# PCB_Task_2020-06-05_09-06-46.net
KiCad netlist of a schematic drawn in EasyEDA
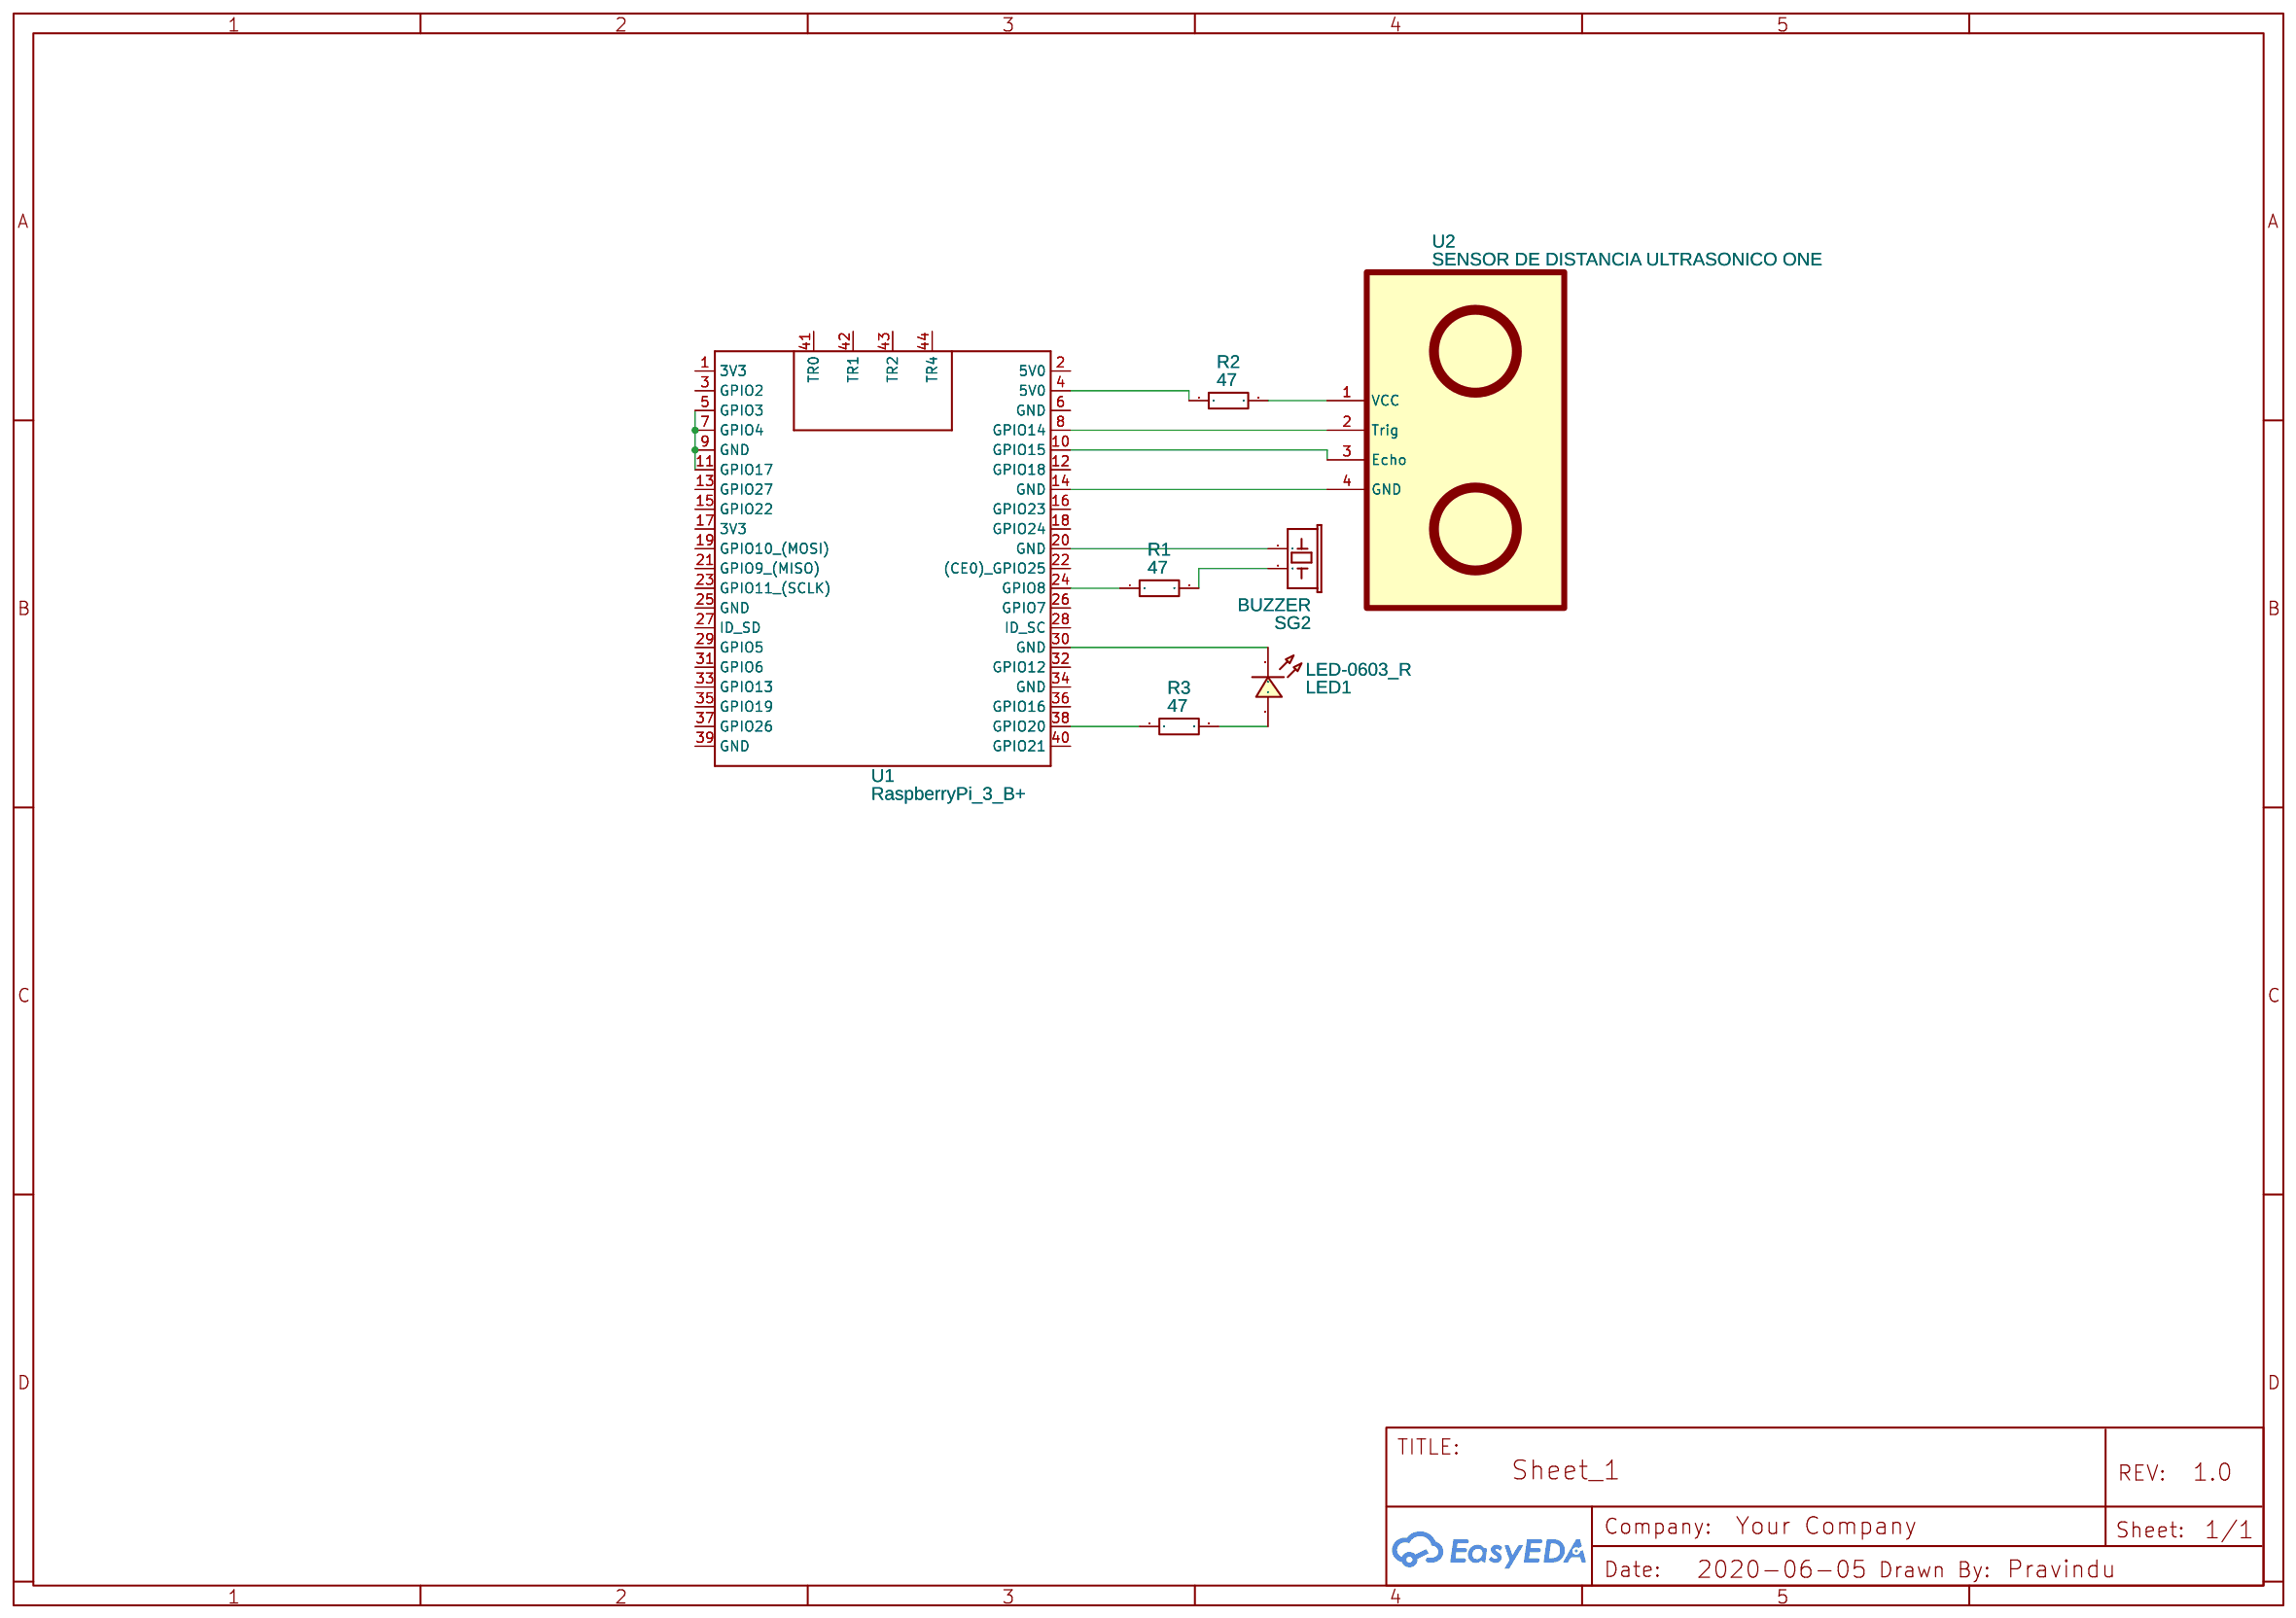
[diagram p0: schematic sheet]

(export (version "E")
  (design (tool "Eeschema 10.0.6"))
  (components
    (comp (ref "LED1")
      (value "LED-0603_R")
      (fields
        (field (name "BOM_Manufacturer Part") "19-217/R6C-AL1M2VY/3T")
        (field (name "BOM_Supplier Part") "C72044")
      )
      (libsource (lib "") (part "LED-0603_R"))
    )
    (comp (ref "R1")
      (value "47")
      (fields
        (field (name "BOM_Manufacturer Part") "KNP2W-47Ω±5% MK型")
        (field (name "BOM_Supplier Part") "C209824")
      )
      (libsource (lib "") (part "47Ω(470) ±5%"))
    )
    (comp (ref "R2")
      (value "47")
      (fields
        (field (name "BOM_Manufacturer Part") "KNP2W-47Ω±5% MK型")
        (field (name "BOM_Supplier Part") "C209824")
      )
      (libsource (lib "") (part "47Ω(470) ±5%"))
    )
    (comp (ref "R3")
      (value "47")
      (fields
        (field (name "BOM_Manufacturer Part") "KNP2W-47Ω±5% MK型")
        (field (name "BOM_Supplier Part") "C209824")
      )
      (libsource (lib "") (part "47Ω(470) ±5%"))
    )
    (comp (ref "SG2") (value "BUZZER") (libsource (lib "") (part "BUZZER")))
    (comp (ref "U1")
      (value "RaspberryPi_3_B+")
      (fields (field (name "BOM_Manufacturer Part") "RaspberryPi 3"))
      (libsource (lib "") (part "RaspberryPi_3_B+"))
    )
    (comp (ref "U2")
      (value "SENSOR DE DISTANCIA ULTRASONICO ONE")
      (libsource (lib "") (part "SENSOR DE DISTANCIA ULTRASONICO ONE"))
    )
  )
  (nets
    (net (code "1") (name "Net-(LED1-Pad1)") (class "Default")
      (node (ref "LED1") (pin "1") (pinfunction "1_1") (pintype "unspecified"))
      (node (ref "R3") (pin "2") (pinfunction "2_2") (pintype "unspecified"))
    )
    (net (code "2") (name "Net-(LED1-Pad2)") (class "Default")
      (node (ref "LED1") (pin "2") (pinfunction "2_2") (pintype "unspecified"))
      (node (ref "U1") (pin "30") (pinfunction "GND_30") (pintype "unspecified"))
    )
    (net (code "3") (name "Net-(R1-Pad2)") (class "Default")
      (node (ref "R1") (pin "2") (pinfunction "2_2") (pintype "unspecified"))
      (node (ref "SG2") (pin "2") (pinfunction "2_2") (pintype "unspecified"))
    )
    (net (code "4") (name "Net-(R2-Pad1)") (class "Default")
      (node (ref "R2") (pin "1") (pinfunction "1_1") (pintype "unspecified"))
      (node (ref "U1") (pin "4") (pinfunction "5V0_4") (pintype "unspecified"))
    )
    (net (code "5") (name "Net-(SG2-Pad1)") (class "Default")
      (node (ref "SG2") (pin "1") (pinfunction "1_1") (pintype "unspecified"))
      (node (ref "U1") (pin "20") (pinfunction "GND_20") (pintype "unspecified"))
    )
    (net (code "6") (name "Net-(U1-GPIO8)") (class "Default")
      (node (ref "R1") (pin "1") (pinfunction "1_1") (pintype "unspecified"))
      (node (ref "U1") (pin "24") (pinfunction "GPIO8_24") (pintype "unspecified"))
    )
    (net (code "7") (name "Net-(U1-GPIO14)") (class "Default")
      (node (ref "U1") (pin "8") (pinfunction "GPIO14_8") (pintype "unspecified"))
      (node (ref "U2") (pin "2") (pinfunction "Trig_2") (pintype "unspecified"))
    )
    (net (code "8") (name "Net-(U1-GPIO15)") (class "Default")
      (node (ref "U1") (pin "10") (pinfunction "GPIO15_10") (pintype "unspecified"))
      (node (ref "U2") (pin "3") (pinfunction "Echo_3") (pintype "unspecified"))
    )
    (net (code "9") (name "Net-(U1-GPIO17)") (class "Default")
      (node (ref "U1") (pin "11") (pinfunction "GPIO17_11") (pintype "unspecified"))
      (node (ref "U1") (pin "5") (pinfunction "GPIO3_5") (pintype "unspecified"))
      (node (ref "U1") (pin "7") (pinfunction "GPIO4_7") (pintype "unspecified"))
      (node (ref "U1") (pin "9") (pinfunction "GND_9") (pintype "unspecified"))
    )
    (net (code "10") (name "Net-(U1-GPIO20)") (class "Default")
      (node (ref "R3") (pin "1") (pinfunction "1_1") (pintype "unspecified"))
      (node (ref "U1") (pin "38") (pinfunction "GPIO20_38") (pintype "unspecified"))
    )
    (net (code "11") (name "Net-(U2-GND)") (class "Default")
      (node (ref "U1") (pin "14") (pinfunction "GND_14") (pintype "unspecified"))
      (node (ref "U2") (pin "4") (pinfunction "GND_4") (pintype "unspecified"))
    )
    (net (code "12") (name "Net-(U2-VCC)") (class "Default")
      (node (ref "R2") (pin "2") (pinfunction "2_2") (pintype "unspecified"))
      (node (ref "U2") (pin "1") (pinfunction "VCC_1") (pintype "unspecified"))
    )
    (net (code "13") (name "unconnected-(U1-(CE0)_GPIO25-Pad22)") (class "Default")
      (node (ref "U1") (pin "22") (pinfunction "(CE0)_GPIO25_22") (pintype "unspecified"))
    )
    (net (code "14") (name "unconnected-(U1-3V3-Pad1)") (class "Default")
      (node (ref "U1") (pin "1") (pinfunction "3V3_1") (pintype "unspecified"))
    )
    (net (code "15") (name "unconnected-(U1-3V3-Pad17)") (class "Default")
      (node (ref "U1") (pin "17") (pinfunction "3V3_17") (pintype "unspecified"))
    )
    (net (code "16") (name "unconnected-(U1-5V0-Pad2)") (class "Default")
      (node (ref "U1") (pin "2") (pinfunction "5V0_2") (pintype "unspecified"))
    )
    (net (code "17") (name "unconnected-(U1-GND-Pad6)") (class "Default")
      (node (ref "U1") (pin "6") (pinfunction "GND_6") (pintype "unspecified"))
    )
    (net (code "18") (name "unconnected-(U1-GND-Pad25)") (class "Default")
      (node (ref "U1") (pin "25") (pinfunction "GND_25") (pintype "unspecified"))
    )
    (net (code "19") (name "unconnected-(U1-GND-Pad34)") (class "Default")
      (node (ref "U1") (pin "34") (pinfunction "GND_34") (pintype "unspecified"))
    )
    (net (code "20") (name "unconnected-(U1-GND-Pad39)") (class "Default")
      (node (ref "U1") (pin "39") (pinfunction "GND_39") (pintype "unspecified"))
    )
    (net (code "21") (name "unconnected-(U1-GPIO2-Pad3)") (class "Default")
      (node (ref "U1") (pin "3") (pinfunction "GPIO2_3") (pintype "unspecified"))
    )
    (net (code "22") (name "unconnected-(U1-GPIO5-Pad29)") (class "Default")
      (node (ref "U1") (pin "29") (pinfunction "GPIO5_29") (pintype "unspecified"))
    )
    (net (code "23") (name "unconnected-(U1-GPIO6-Pad31)") (class "Default")
      (node (ref "U1") (pin "31") (pinfunction "GPIO6_31") (pintype "unspecified"))
    )
    (net (code "24") (name "unconnected-(U1-GPIO7-Pad26)") (class "Default")
      (node (ref "U1") (pin "26") (pinfunction "GPIO7_26") (pintype "unspecified"))
    )
    (net (code "25") (name "unconnected-(U1-GPIO9_(MISO)-Pad21)") (class "Default")
      (node (ref "U1") (pin "21") (pinfunction "GPIO9_(MISO)_21") (pintype "unspecified"))
    )
    (net (code "26") (name "unconnected-(U1-GPIO10_(MOSI)-Pad19)") (class "Default")
      (node (ref "U1") (pin "19") (pinfunction "GPIO10_(MOSI)_19") (pintype "unspecified"))
    )
    (net (code "27") (name "unconnected-(U1-GPIO11_(SCLK)-Pad23)") (class "Default")
      (node (ref "U1") (pin "23") (pinfunction "GPIO11_(SCLK)_23") (pintype "unspecified"))
    )
    (net (code "28") (name "unconnected-(U1-GPIO12-Pad32)") (class "Default")
      (node (ref "U1") (pin "32") (pinfunction "GPIO12_32") (pintype "unspecified"))
    )
    (net (code "29") (name "unconnected-(U1-GPIO13-Pad33)") (class "Default")
      (node (ref "U1") (pin "33") (pinfunction "GPIO13_33") (pintype "unspecified"))
    )
    (net (code "30") (name "unconnected-(U1-GPIO16-Pad36)") (class "Default")
      (node (ref "U1") (pin "36") (pinfunction "GPIO16_36") (pintype "unspecified"))
    )
    (net (code "31") (name "unconnected-(U1-GPIO18-Pad12)") (class "Default")
      (node (ref "U1") (pin "12") (pinfunction "GPIO18_12") (pintype "unspecified"))
    )
    (net (code "32") (name "unconnected-(U1-GPIO19-Pad35)") (class "Default")
      (node (ref "U1") (pin "35") (pinfunction "GPIO19_35") (pintype "unspecified"))
    )
    (net (code "33") (name "unconnected-(U1-GPIO21-Pad40)") (class "Default")
      (node (ref "U1") (pin "40") (pinfunction "GPIO21_40") (pintype "unspecified"))
    )
    (net (code "34") (name "unconnected-(U1-GPIO22-Pad15)") (class "Default")
      (node (ref "U1") (pin "15") (pinfunction "GPIO22_15") (pintype "unspecified"))
    )
    (net (code "35") (name "unconnected-(U1-GPIO23-Pad16)") (class "Default")
      (node (ref "U1") (pin "16") (pinfunction "GPIO23_16") (pintype "unspecified"))
    )
    (net (code "36") (name "unconnected-(U1-GPIO24-Pad18)") (class "Default")
      (node (ref "U1") (pin "18") (pinfunction "GPIO24_18") (pintype "unspecified"))
    )
    (net (code "37") (name "unconnected-(U1-GPIO26-Pad37)") (class "Default")
      (node (ref "U1") (pin "37") (pinfunction "GPIO26_37") (pintype "unspecified"))
    )
    (net (code "38") (name "unconnected-(U1-GPIO27-Pad13)") (class "Default")
      (node (ref "U1") (pin "13") (pinfunction "GPIO27_13") (pintype "unspecified"))
    )
    (net (code "39") (name "unconnected-(U1-ID_SC-Pad28)") (class "Default")
      (node (ref "U1") (pin "28") (pinfunction "ID_SC_28") (pintype "unspecified"))
    )
    (net (code "40") (name "unconnected-(U1-ID_SD-Pad27)") (class "Default")
      (node (ref "U1") (pin "27") (pinfunction "ID_SD_27") (pintype "unspecified"))
    )
    (net (code "41") (name "unconnected-(U1-TR0-Pad41)") (class "Default")
      (node (ref "U1") (pin "41") (pinfunction "TR0_41") (pintype "unspecified"))
    )
    (net (code "42") (name "unconnected-(U1-TR1-Pad42)") (class "Default")
      (node (ref "U1") (pin "42") (pinfunction "TR1_42") (pintype "unspecified"))
    )
    (net (code "43") (name "unconnected-(U1-TR2-Pad43)") (class "Default")
      (node (ref "U1") (pin "43") (pinfunction "TR2_43") (pintype "unspecified"))
    )
    (net (code "44") (name "unconnected-(U1-TR4-Pad44)") (class "Default")
      (node (ref "U1") (pin "44") (pinfunction "TR4_44") (pintype "unspecified"))
    )
  )
)
